# AnalogOut.net
KiCad netlist of a schematic drawn in Altium Designer
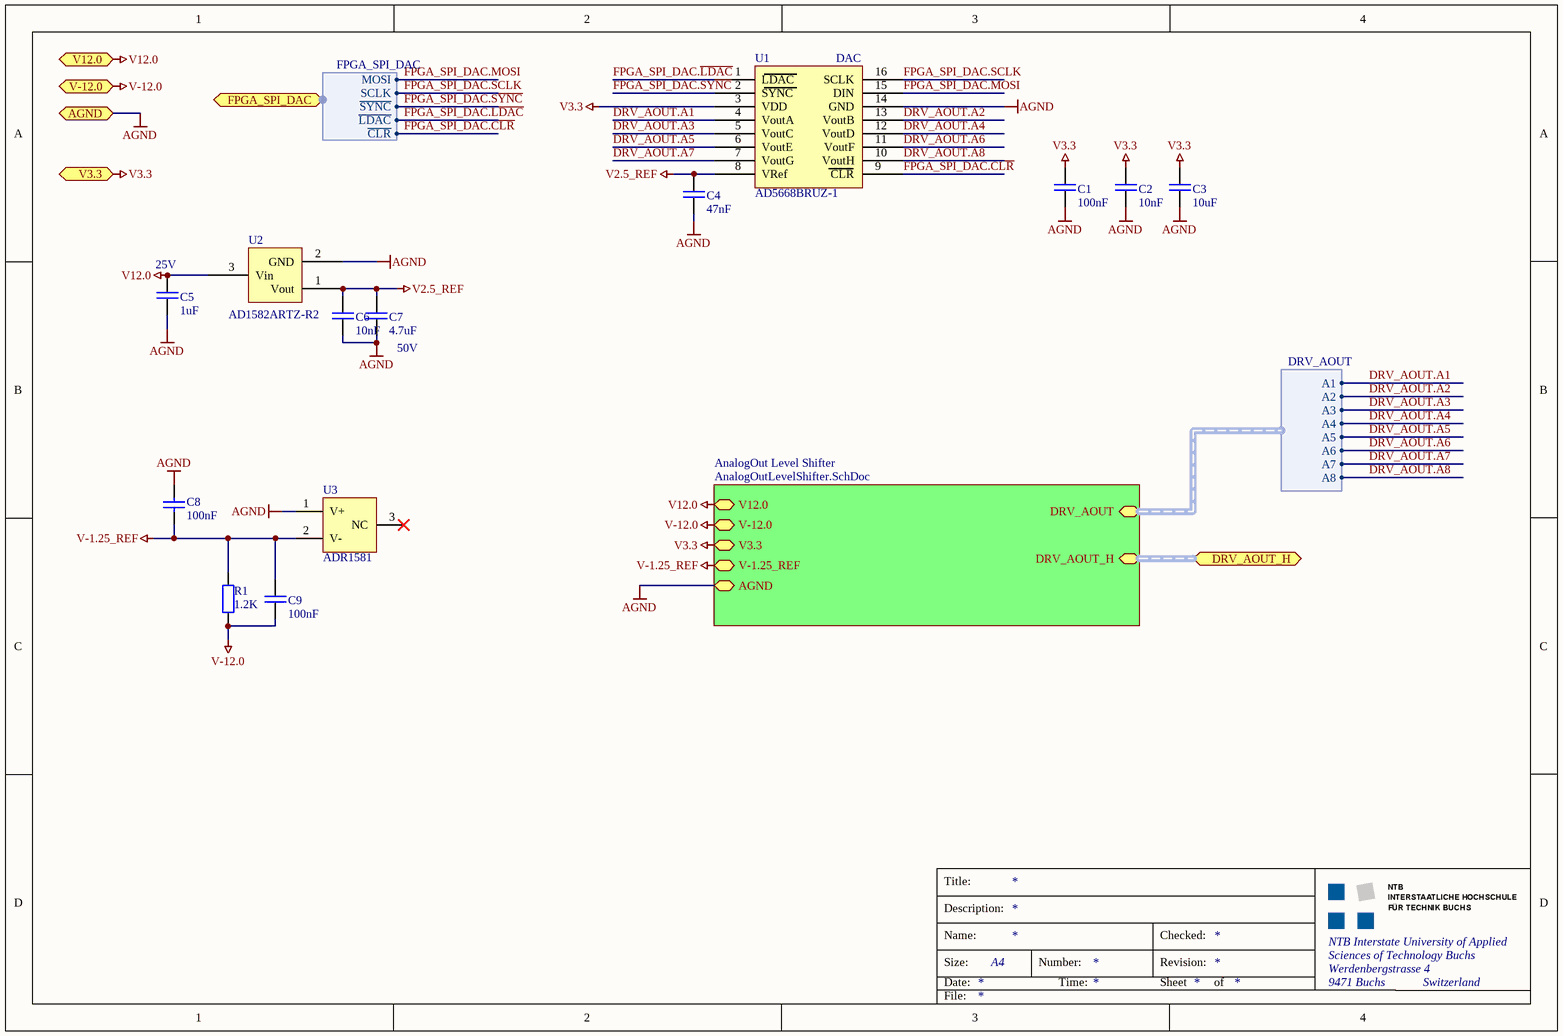
[diagram p0: AnalogOut.SchDoc]

(export (version "E")
  (design (tool "Eeschema 10.0.6"))
  (components
    (comp (ref "C1")
      (value "100nF")
      (footprint "0603_3D")
      (description "Capacitor")
      (fields (field (name "#PUBLISHER") "Dr. A. Heinzelmann"))
      (libsource (lib "PartLib") (part "C"))
    )
    (comp (ref "C2")
      (value "10nF")
      (footprint "0603_3D")
      (description "Capacitor")
      (fields (field (name "#PUBLISHER") "Dr. A. Heinzelmann"))
      (libsource (lib "PartLib") (part "C"))
    )
    (comp (ref "C3")
      (value "10uF")
      (footprint "0603_3D")
      (description "Capacitor")
      (fields (field (name "#PUBLISHER") "Dr. A. Heinzelmann"))
      (libsource (lib "PartLib") (part "C"))
    )
    (comp (ref "C4")
      (value "47nF")
      (footprint "0603_3D")
      (description "Capacitor")
      (fields (field (name "#PUBLISHER") "Dr. A. Heinzelmann"))
      (libsource (lib "PartLib") (part "C"))
    )
    (comp (ref "C5")
      (value "1uF")
      (footprint "0603_3D")
      (description "Capacitor")
      (fields (field (name "VOLTAGE MAXIMUM") "25V") (field (name "#PUBLISHER") "Dr. A. Heinzelmann"))
      (libsource (lib "PartLib") (part "C"))
    )
    (comp (ref "C6")
      (value "10nF")
      (footprint "0603_3D")
      (description "Capacitor")
      (fields (field (name "#PUBLISHER") "Dr. A. Heinzelmann"))
      (libsource (lib "PartLib") (part "C"))
    )
    (comp (ref "C7")
      (value "4.7uF")
      (footprint "1206")
      (description "Capacitor")
      (fields (field (name "VOLTAGE MAXIMUM") "50V") (field (name "#PUBLISHER") "Dr. A. Heinzelmann"))
      (libsource (lib "PartLib") (part "C"))
    )
    (comp (ref "C8")
      (value "100nF")
      (footprint "0603_3D")
      (description "Capacitor")
      (fields (field (name "#PUBLISHER") "Dr. A. Heinzelmann"))
      (libsource (lib "ELE-LIB") (part "C"))
    )
    (comp (ref "C9")
      (value "100nF")
      (footprint "0603_3D")
      (description "Capacitor")
      (fields (field (name "#PUBLISHER") "Dr. A. Heinzelmann"))
      (libsource (lib "PartLib") (part "C"))
    )
    (comp (ref "R1")
      (value "1.2K")
      (footprint "0603")
      (description "Resistor")
      (fields (field (name "#PUBLISHER") "Dr. A. Heinzelmann"))
      (libsource (lib "PartLib") (part "R"))
    )
    (comp (ref "U1")
      (value "AD5668BRUZ-1")
      (footprint "TSSOP16-W")
      (libsource (lib "PartLib") (part "AD5668BRUZ-1"))
    )
    (comp (ref "U2")
      (value "AD1582ARTZ-R2")
      (footprint "SOT23")
      (libsource (lib "PartLib") (part "AD1582ARTZ-R2"))
    )
    (comp (ref "U3") (value "ADR1581") (footprint "SOT23") (libsource (lib "PartLib") (part "ADR1581")))
  )
  (nets
    (net (code "4") (name "/DRV_AOUT.A1") (class "Default")
      (node (ref "U1") (pin "4") (pinfunction "VoutA_4") (pintype "passive"))
    )
    (net (code "5") (name "/DRV_AOUT.A2") (class "Default")
      (node (ref "U1") (pin "13") (pinfunction "VoutB_13") (pintype "passive"))
    )
    (net (code "6") (name "/DRV_AOUT.A3") (class "Default")
      (node (ref "U1") (pin "5") (pinfunction "VoutC_5") (pintype "passive"))
    )
    (net (code "7") (name "/DRV_AOUT.A4") (class "Default")
      (node (ref "U1") (pin "12") (pinfunction "VoutD_12") (pintype "passive"))
    )
    (net (code "8") (name "/DRV_AOUT.A5") (class "Default")
      (node (ref "U1") (pin "6") (pinfunction "VoutE_6") (pintype "passive"))
    )
    (net (code "9") (name "/DRV_AOUT.A6") (class "Default")
      (node (ref "U1") (pin "11") (pinfunction "VoutF_11") (pintype "passive"))
    )
    (net (code "10") (name "/DRV_AOUT.A7") (class "Default")
      (node (ref "U1") (pin "7") (pinfunction "VoutG_7") (pintype "passive"))
    )
    (net (code "11") (name "/DRV_AOUT.A8") (class "Default")
      (node (ref "U1") (pin "10") (pinfunction "VoutH_10") (pintype "passive"))
    )
    (net (code "13") (name "/FPGA_SPI_DAC.MOSI") (class "Default")
      (node (ref "U1") (pin "15") (pinfunction "DIN_15") (pintype "passive"))
    )
    (net (code "14") (name "/FPGA_SPI_DAC.SCLK") (class "Default")
      (node (ref "U1") (pin "16") (pinfunction "SCLK_16") (pintype "passive"))
    )
    (net (code "15") (name "/FPGA_SPI_DAC.~{CLR}") (class "Default")
      (node (ref "U1") (pin "9") (pinfunction "CLR_9") (pintype "passive"))
    )
    (net (code "16") (name "/FPGA_SPI_DAC.~{LDAC}") (class "Default")
      (node (ref "U1") (pin "1") (pinfunction "LDAC_1") (pintype "passive"))
    )
    (net (code "17") (name "/FPGA_SPI_DAC.~{SYNC}") (class "Default")
      (node (ref "U1") (pin "2") (pinfunction "SYNC_2") (pintype "passive"))
    )
    (net (code "20") (name "AGND") (class "Default")
      (node (ref "C1") (pin "2") (pinfunction "2_2") (pintype "passive"))
      (node (ref "C2") (pin "2") (pinfunction "2_2") (pintype "passive"))
      (node (ref "C3") (pin "2") (pinfunction "2_2") (pintype "passive"))
      (node (ref "C4") (pin "2") (pinfunction "2_2") (pintype "passive"))
      (node (ref "C5") (pin "1") (pinfunction "1_1") (pintype "passive"))
      (node (ref "C6") (pin "2") (pinfunction "2_2") (pintype "passive"))
      (node (ref "C7") (pin "2") (pinfunction "2_2") (pintype "passive"))
      (node (ref "C8") (pin "2") (pinfunction "2_2") (pintype "passive"))
      (node (ref "U1") (pin "14") (pinfunction "GND_14") (pintype "passive"))
      (node (ref "U2") (pin "2") (pinfunction "GND_2") (pintype "passive"))
      (node (ref "U3") (pin "1") (pinfunction "V+_1") (pintype "passive"))
    )
    (net (code "21") (name "V-1.25_REF") (class "Default")
      (node (ref "C8") (pin "1") (pinfunction "1_1") (pintype "passive"))
      (node (ref "C9") (pin "2") (pinfunction "2_2") (pintype "passive"))
      (node (ref "R1") (pin "2") (pinfunction "2_2") (pintype "passive"))
      (node (ref "U3") (pin "2") (pinfunction "V-_2") (pintype "passive"))
    )
    (net (code "22") (name "V-12.0") (class "Default")
      (node (ref "C9") (pin "1") (pinfunction "1_1") (pintype "passive"))
      (node (ref "R1") (pin "1") (pinfunction "1_1") (pintype "passive"))
    )
    (net (code "23") (name "V2.5_REF") (class "Default")
      (node (ref "C4") (pin "1") (pinfunction "1_1") (pintype "passive"))
      (node (ref "C6") (pin "1") (pinfunction "1_1") (pintype "passive"))
      (node (ref "C7") (pin "1") (pinfunction "1_1") (pintype "passive"))
      (node (ref "U1") (pin "8") (pinfunction "VRef_8") (pintype "passive"))
      (node (ref "U2") (pin "1") (pinfunction "Vout_1") (pintype "passive"))
    )
    (net (code "24") (name "V3.3") (class "Default")
      (node (ref "C1") (pin "1") (pinfunction "1_1") (pintype "passive"))
      (node (ref "C2") (pin "1") (pinfunction "1_1") (pintype "passive"))
      (node (ref "C3") (pin "1") (pinfunction "1_1") (pintype "passive"))
      (node (ref "U1") (pin "3") (pinfunction "VDD_3") (pintype "passive"))
    )
    (net (code "25") (name "V12.0") (class "Default")
      (node (ref "C5") (pin "2") (pinfunction "2_2") (pintype "passive"))
      (node (ref "U2") (pin "3") (pinfunction "Vin_3") (pintype "passive"))
    )
    (net (code "26") (name "unconnected-(U3-NC-Pad3)") (class "Default")
      (node (ref "U3") (pin "3") (pinfunction "NC_3") (pintype "passive+no_connect"))
    )
  )
)
